# SparkX_smol_Environmental.net
KiCad netlist of a schematic drawn in EAGLE
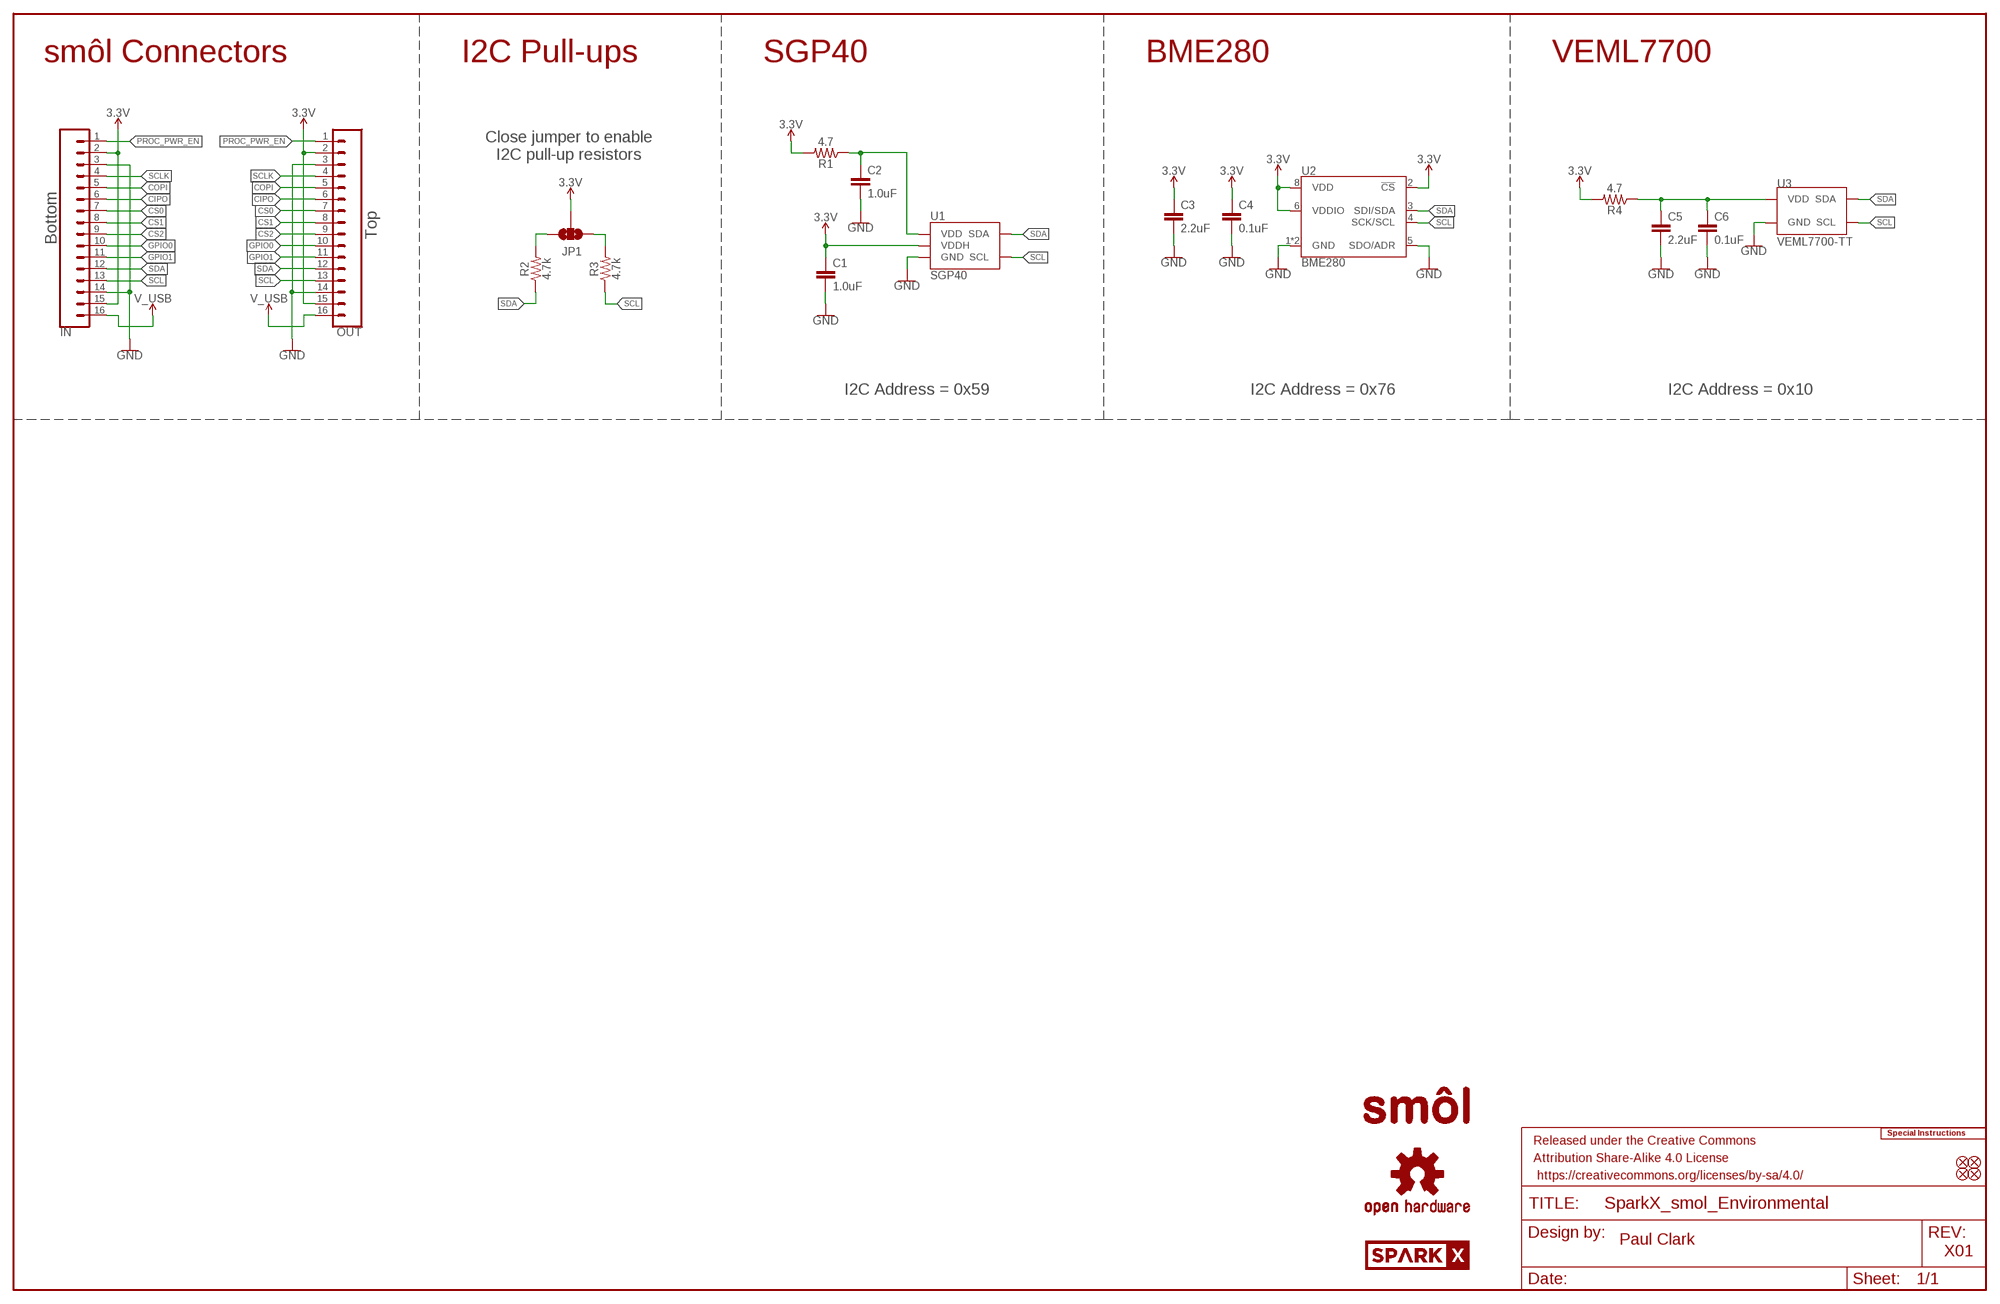
[diagram p0: schematic, sheet 1]

(export (version "E")
  (design (tool "Eeschema 10.0.6"))
  (components
    (comp (ref "C1")
      (value "1.0uF")
      (footprint "eagle-import:0402-TIGHT")
      (libsource (lib "eagle-import") (part "1.0UF-0402T-16V-10%"))
    )
    (comp (ref "C2")
      (value "1.0uF")
      (footprint "eagle-import:0402-TIGHT")
      (libsource (lib "eagle-import") (part "1.0UF-0402T-16V-10%"))
    )
    (comp (ref "C3")
      (value "2.2uF")
      (footprint "eagle-import:0402-TIGHT")
      (libsource (lib "eagle-import") (part "2.2UF-0402_TIGHT-10V-10%-X5R"))
    )
    (comp (ref "C4")
      (value "0.1uF")
      (footprint "eagle-import:0402-TIGHT")
      (libsource (lib "eagle-import") (part "0.1UF-0402T-6.3V-10%-X7R"))
    )
    (comp (ref "C5")
      (value "2.2uF")
      (footprint "eagle-import:0402-TIGHT")
      (libsource (lib "eagle-import") (part "2.2UF-0402_TIGHT-10V-10%-X5R"))
    )
    (comp (ref "C6")
      (value "0.1uF")
      (footprint "eagle-import:0402-TIGHT")
      (libsource (lib "eagle-import") (part "0.1UF-0402T-6.3V-10%-X7R"))
    )
    (comp (ref "FD1")
      (value "FIDUCIALUFIDUCIAL")
      (footprint "eagle-import:FIDUCIAL-MICRO")
      (libsource (lib "eagle-import") (part "FIDUCIALUFIDUCIAL"))
    )
    (comp (ref "FD2")
      (value "FIDUCIALUFIDUCIAL")
      (footprint "eagle-import:FIDUCIAL-MICRO")
      (libsource (lib "eagle-import") (part "FIDUCIALUFIDUCIAL"))
    )
    (comp (ref "FD3")
      (value "FIDUCIALUFIDUCIAL")
      (footprint "eagle-import:FIDUCIAL-MICRO")
      (libsource (lib "eagle-import") (part "FIDUCIALUFIDUCIAL"))
    )
    (comp (ref "FD4")
      (value "FIDUCIALUFIDUCIAL")
      (footprint "eagle-import:FIDUCIAL-MICRO")
      (libsource (lib "eagle-import") (part "FIDUCIALUFIDUCIAL"))
    )
    (comp (ref "FRAME1")
      (value "FRAME-LEDGER")
      (footprint "eagle-import:CREATIVE_COMMONS")
      (libsource (lib "eagle-import") (part "FRAME-LEDGER"))
    )
    (comp (ref "IN")
      (value "CONN_16FPC_16_0.5MM")
      (footprint "eagle-import:FPC_16_0.5MM")
      (libsource (lib "eagle-import") (part "CONN_16FPC_16_0.5MM"))
    )
    (comp (ref "JP1")
      (value "JUMPER-SMT_3_NO_SILK")
      (footprint "eagle-import:SMT-JUMPER_3_NO_SILK")
      (libsource (lib "eagle-import") (part "JUMPER-SMT_3_NO_SILK"))
    )
    (comp (ref "LOGO1")
      (value "SPECIAL_INSTRUCTIONS-ORDERING")
      (footprint "eagle-import:ORDERING_INSTRUCTIONS")
      (libsource (lib "eagle-import") (part "SPECIAL_INSTRUCTIONS-ORDERING"))
    )
    (comp (ref "LOGO2")
      (value "OSHW-LOGOMINI")
      (footprint "eagle-import:OSHW-LOGO-MINI")
      (libsource (lib "eagle-import") (part "OSHW-LOGOMINI"))
    )
    (comp (ref "LOGO3")
      (value "OSHW-LOGOMINI")
      (footprint "eagle-import:OSHW-LOGO-MINI")
      (libsource (lib "eagle-import") (part "OSHW-LOGOMINI"))
    )
    (comp (ref "OUT")
      (value "CONN_16FPC_16_0.5MM")
      (footprint "eagle-import:FPC_16_0.5MM")
      (libsource (lib "eagle-import") (part "CONN_16FPC_16_0.5MM"))
    )
    (comp (ref "R1")
      (value "4.7")
      (footprint "eagle-import:0402-TIGHT")
      (libsource (lib "eagle-import") (part "4.7OHM-0402T-1/16W-1%"))
    )
    (comp (ref "R2")
      (value "4.7k")
      (footprint "eagle-import:0402-TIGHT")
      (libsource (lib "eagle-import") (part "4.7KOHM-0402T-1/16W-1%"))
    )
    (comp (ref "R3")
      (value "4.7k")
      (footprint "eagle-import:0402-TIGHT")
      (libsource (lib "eagle-import") (part "4.7KOHM-0402T-1/16W-1%"))
    )
    (comp (ref "R4")
      (value "4.7")
      (footprint "eagle-import:0402-TIGHT")
      (libsource (lib "eagle-import") (part "4.7OHM-0402T-1/16W-1%"))
    )
    (comp (ref "U$1")
      (value "SPARKX-LOGO3")
      (footprint "eagle-import:SPARKX-SMALL")
      (libsource (lib "eagle-import") (part "SPARKX-LOGO3"))
    )
    (comp (ref "U$3")
      (value "SMOL_LOGOSMALL")
      (footprint "eagle-import:SMOL_SMALL")
      (libsource (lib "eagle-import") (part "SMOL_LOGOSMALL"))
    )
    (comp (ref "U$9")
      (value "SMOL_LOGOSMALL")
      (footprint "eagle-import:SMOL_SMALL")
      (libsource (lib "eagle-import") (part "SMOL_LOGOSMALL"))
    )
    (comp (ref "U1")
      (value "SGP40")
      (footprint "eagle-import:SGP40")
      (fields (field (name "DIGIKEY_PART") "1649-SGP40-D-R4CT-ND"))
      (libsource (lib "eagle-import") (part "SGP40"))
    )
    (comp (ref "U2")
      (value "BME280")
      (footprint "eagle-import:LGA-8-2.5X2.5")
      (libsource (lib "eagle-import") (part "BME280"))
    )
    (comp (ref "U3")
      (value "VEML7700-TT")
      (footprint "eagle-import:VEML7700_TT")
      (libsource (lib "eagle-import") (part "VEML7700-TT"))
    )
  )
  (nets
    (net (code "1") (name "3.3V") (class "Default")
      (node (ref "C1") (pin "1") (pinfunction "1_1") (pintype "passive"))
      (node (ref "C3") (pin "1") (pinfunction "1_1") (pintype "passive"))
      (node (ref "C4") (pin "1") (pinfunction "1_1") (pintype "passive"))
      (node (ref "IN") (pin "15") (pinfunction "15_15") (pintype "passive"))
      (node (ref "IN") (pin "2") (pinfunction "2_2") (pintype "passive"))
      (node (ref "JP1") (pin "2") (pinfunction "2_2") (pintype "passive"))
      (node (ref "OUT") (pin "15") (pinfunction "15_15") (pintype "passive"))
      (node (ref "OUT") (pin "2") (pinfunction "2_2") (pintype "passive"))
      (node (ref "R1") (pin "2") (pinfunction "2_2") (pintype "passive"))
      (node (ref "R4") (pin "2") (pinfunction "2_2") (pintype "passive"))
      (node (ref "U1") (pin "5") (pinfunction "VDDH_5") (pintype "power_in"))
      (node (ref "U2") (pin "2") (pinfunction "~{CS}_2") (pintype "bidirectional"))
      (node (ref "U2") (pin "6") (pinfunction "VDDIO_6") (pintype "bidirectional"))
      (node (ref "U2") (pin "8") (pinfunction "VDD_8") (pintype "bidirectional"))
    )
    (net (code "2") (name "CIPO") (class "Default")
      (node (ref "IN") (pin "6") (pinfunction "6_6") (pintype "passive"))
      (node (ref "OUT") (pin "6") (pinfunction "6_6") (pintype "passive"))
    )
    (net (code "3") (name "COPI") (class "Default")
      (node (ref "IN") (pin "5") (pinfunction "5_5") (pintype "passive"))
      (node (ref "OUT") (pin "5") (pinfunction "5_5") (pintype "passive"))
    )
    (net (code "4") (name "CS0") (class "Default")
      (node (ref "IN") (pin "7") (pinfunction "7_7") (pintype "passive"))
      (node (ref "OUT") (pin "7") (pinfunction "7_7") (pintype "passive"))
    )
    (net (code "5") (name "CS1") (class "Default")
      (node (ref "IN") (pin "8") (pinfunction "8_8") (pintype "passive"))
      (node (ref "OUT") (pin "8") (pinfunction "8_8") (pintype "passive"))
    )
    (net (code "6") (name "CS2") (class "Default")
      (node (ref "IN") (pin "9") (pinfunction "9_9") (pintype "passive"))
      (node (ref "OUT") (pin "9") (pinfunction "9_9") (pintype "passive"))
    )
    (net (code "7") (name "GND") (class "Default")
      (node (ref "C1") (pin "2") (pinfunction "2_2") (pintype "passive"))
      (node (ref "C2") (pin "2") (pinfunction "2_2") (pintype "passive"))
      (node (ref "C3") (pin "2") (pinfunction "2_2") (pintype "passive"))
      (node (ref "C4") (pin "2") (pinfunction "2_2") (pintype "passive"))
      (node (ref "C5") (pin "2") (pinfunction "2_2") (pintype "passive"))
      (node (ref "C6") (pin "2") (pinfunction "2_2") (pintype "passive"))
      (node (ref "IN") (pin "14") (pinfunction "14_14") (pintype "passive"))
      (node (ref "IN") (pin "3") (pinfunction "3_3") (pintype "passive"))
      (node (ref "OUT") (pin "14") (pinfunction "14_14") (pintype "passive"))
      (node (ref "OUT") (pin "3") (pinfunction "3_3") (pintype "passive"))
      (node (ref "U1") (pin "2") (pinfunction "GND_2") (pintype "power_in"))
      (node (ref "U1") (pin "4") (pinfunction "GND_4") (pintype "power_in"))
      (node (ref "U1") (pin "DIEPAD") (pinfunction "GND_DIEPAD") (pintype "power_in"))
      (node (ref "U2") (pin "1") (pinfunction "GND_1") (pintype "bidirectional"))
      (node (ref "U2") (pin "5") (pinfunction "SDO/ADR_5") (pintype "bidirectional"))
      (node (ref "U2") (pin "7") (pinfunction "GND_7") (pintype "bidirectional"))
      (node (ref "U3") (pin "3") (pinfunction "GND_3") (pintype "power_in"))
    )
    (net (code "8") (name "GPIO0") (class "Default")
      (node (ref "IN") (pin "10") (pinfunction "10_10") (pintype "passive"))
      (node (ref "OUT") (pin "10") (pinfunction "10_10") (pintype "passive"))
    )
    (net (code "9") (name "GPIO1") (class "Default")
      (node (ref "IN") (pin "11") (pinfunction "11_11") (pintype "passive"))
      (node (ref "OUT") (pin "11") (pinfunction "11_11") (pintype "passive"))
    )
    (net (code "10") (name "Net-(JP1-Pad1)") (class "Default")
      (node (ref "JP1") (pin "1") (pinfunction "1_1") (pintype "passive"))
      (node (ref "R3") (pin "2") (pinfunction "2_2") (pintype "passive"))
    )
    (net (code "11") (name "Net-(JP1-Pad3)") (class "Default")
      (node (ref "JP1") (pin "3") (pinfunction "3_3") (pintype "passive"))
      (node (ref "R2") (pin "2") (pinfunction "2_2") (pintype "passive"))
    )
    (net (code "12") (name "Net-(U1-VDD)") (class "Default")
      (node (ref "C2") (pin "1") (pinfunction "1_1") (pintype "passive"))
      (node (ref "R1") (pin "1") (pinfunction "1_1") (pintype "passive"))
      (node (ref "U1") (pin "1") (pinfunction "VDD_1") (pintype "power_in"))
    )
    (net (code "13") (name "Net-(U3-VDD)") (class "Default")
      (node (ref "C5") (pin "1") (pinfunction "1_1") (pintype "passive"))
      (node (ref "C6") (pin "1") (pinfunction "1_1") (pintype "passive"))
      (node (ref "R4") (pin "1") (pinfunction "1_1") (pintype "passive"))
      (node (ref "U3") (pin "2") (pinfunction "VDD_2") (pintype "power_in"))
    )
    (net (code "14") (name "PROC_PWR_EN") (class "Default")
      (node (ref "IN") (pin "1") (pinfunction "1_1") (pintype "passive"))
      (node (ref "OUT") (pin "1") (pinfunction "1_1") (pintype "passive"))
    )
    (net (code "15") (name "SCL") (class "Default")
      (node (ref "IN") (pin "13") (pinfunction "13_13") (pintype "passive"))
      (node (ref "OUT") (pin "13") (pinfunction "13_13") (pintype "passive"))
      (node (ref "R3") (pin "1") (pinfunction "1_1") (pintype "passive"))
      (node (ref "U1") (pin "6") (pinfunction "SCL_6") (pintype "bidirectional"))
      (node (ref "U2") (pin "4") (pinfunction "SCK/SCL_4") (pintype "bidirectional"))
      (node (ref "U3") (pin "1") (pinfunction "SCL_1") (pintype "bidirectional"))
    )
    (net (code "16") (name "SCLK") (class "Default")
      (node (ref "IN") (pin "4") (pinfunction "4_4") (pintype "passive"))
      (node (ref "OUT") (pin "4") (pinfunction "4_4") (pintype "passive"))
    )
    (net (code "17") (name "SDA") (class "Default")
      (node (ref "IN") (pin "12") (pinfunction "12_12") (pintype "passive"))
      (node (ref "OUT") (pin "12") (pinfunction "12_12") (pintype "passive"))
      (node (ref "R2") (pin "1") (pinfunction "1_1") (pintype "passive"))
      (node (ref "U1") (pin "3") (pinfunction "SDA_3") (pintype "bidirectional"))
      (node (ref "U2") (pin "3") (pinfunction "SDI/SDA_3") (pintype "bidirectional"))
      (node (ref "U3") (pin "4") (pinfunction "SDA_4") (pintype "bidirectional"))
    )
    (net (code "18") (name "V_USB") (class "Default")
      (node (ref "IN") (pin "16") (pinfunction "16_16") (pintype "passive"))
      (node (ref "OUT") (pin "16") (pinfunction "16_16") (pintype "passive"))
    )
  )
)
